# in-15a-single.net
KiCad netlist of a schematic drawn in EAGLE
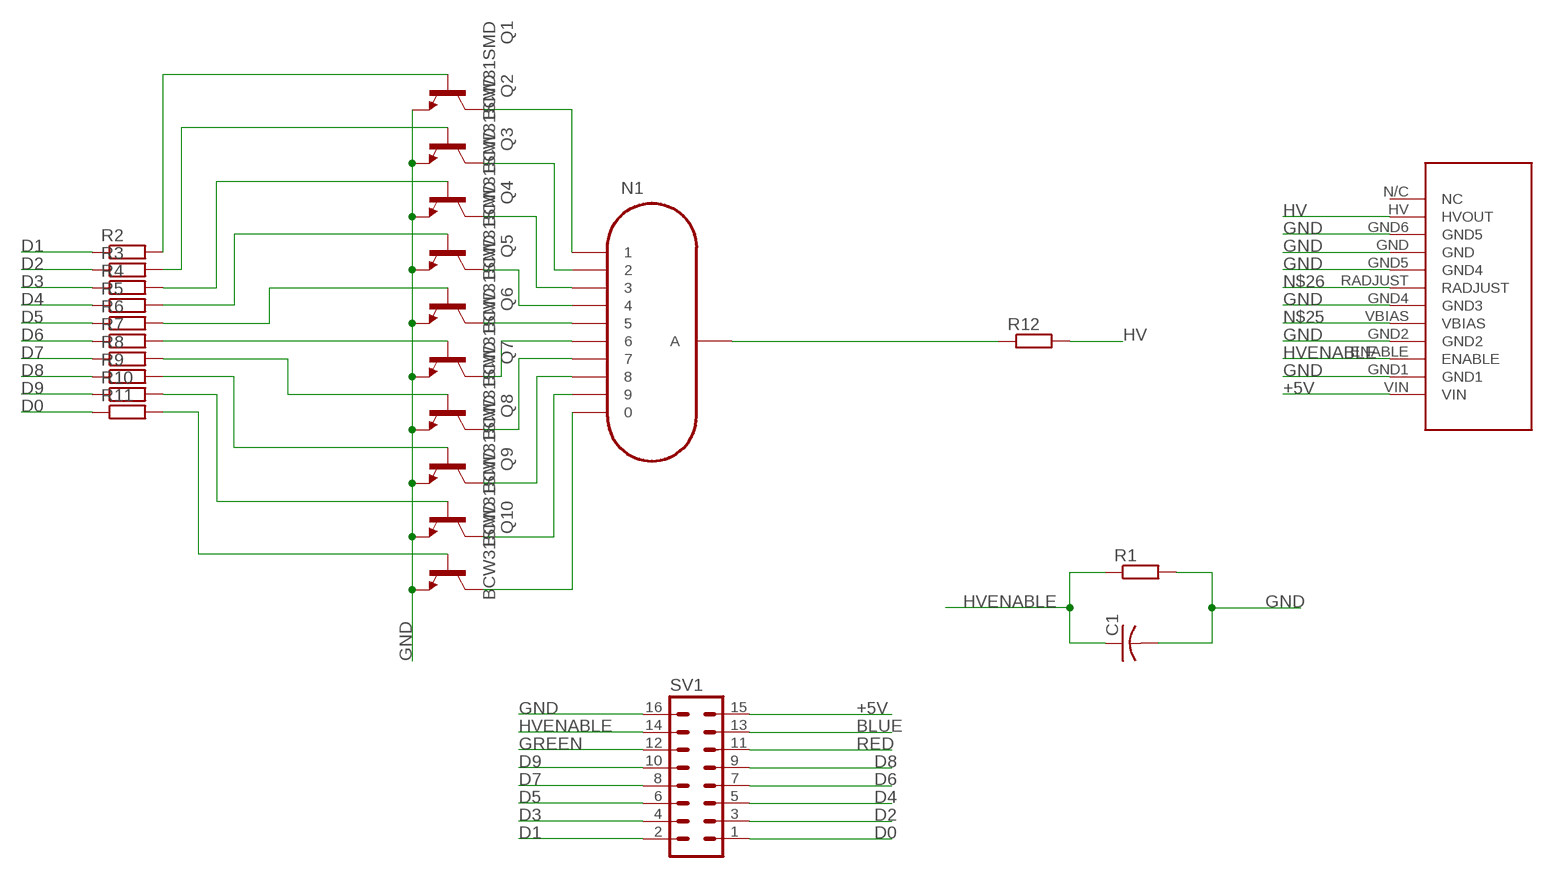
[diagram p0: schematic, sheet 1]

(export (version "E")
  (design (tool "Eeschema 10.0.6"))
  (components
    (comp (ref "C1")
      (value "C-USC0805")
      (footprint "eagle-import:C0805")
      (libsource (lib "eagle-import") (part "C-USC0805"))
    )
    (comp (ref "N1")
      (value "IN-12A")
      (footprint "eagle-import:IN-12-BIG")
      (libsource (lib "eagle-import") (part "IN-12A"))
    )
    (comp (ref "Q1")
      (value "BCW31SMD")
      (footprint "eagle-import:SOT23-BEC")
      (libsource (lib "eagle-import") (part "BCW31SMD"))
    )
    (comp (ref "Q2")
      (value "BCW31SMD")
      (footprint "eagle-import:SOT23-BEC")
      (libsource (lib "eagle-import") (part "BCW31SMD"))
    )
    (comp (ref "Q3")
      (value "BCW31SMD")
      (footprint "eagle-import:SOT23-BEC")
      (libsource (lib "eagle-import") (part "BCW31SMD"))
    )
    (comp (ref "Q4")
      (value "BCW31SMD")
      (footprint "eagle-import:SOT23-BEC")
      (libsource (lib "eagle-import") (part "BCW31SMD"))
    )
    (comp (ref "Q5")
      (value "BCW31SMD")
      (footprint "eagle-import:SOT23-BEC")
      (libsource (lib "eagle-import") (part "BCW31SMD"))
    )
    (comp (ref "Q6")
      (value "BCW31SMD")
      (footprint "eagle-import:SOT23-BEC")
      (libsource (lib "eagle-import") (part "BCW31SMD"))
    )
    (comp (ref "Q7")
      (value "BCW31SMD")
      (footprint "eagle-import:SOT23-BEC")
      (libsource (lib "eagle-import") (part "BCW31SMD"))
    )
    (comp (ref "Q8")
      (value "BCW31SMD")
      (footprint "eagle-import:SOT23-BEC")
      (libsource (lib "eagle-import") (part "BCW31SMD"))
    )
    (comp (ref "Q9")
      (value "BCW31SMD")
      (footprint "eagle-import:SOT23-BEC")
      (libsource (lib "eagle-import") (part "BCW31SMD"))
    )
    (comp (ref "Q10")
      (value "BCW31SMD")
      (footprint "eagle-import:SOT23-BEC")
      (libsource (lib "eagle-import") (part "BCW31SMD"))
    )
    (comp (ref "R1")
      (value "R-EU_M0805")
      (footprint "eagle-import:M0805")
      (libsource (lib "eagle-import") (part "R-EU_M0805"))
    )
    (comp (ref "R2")
      (value "R-EU_M0805")
      (footprint "eagle-import:M0805")
      (libsource (lib "eagle-import") (part "R-EU_M0805"))
    )
    (comp (ref "R3")
      (value "R-EU_M0805")
      (footprint "eagle-import:M0805")
      (libsource (lib "eagle-import") (part "R-EU_M0805"))
    )
    (comp (ref "R4")
      (value "R-EU_M0805")
      (footprint "eagle-import:M0805")
      (libsource (lib "eagle-import") (part "R-EU_M0805"))
    )
    (comp (ref "R5")
      (value "R-EU_M0805")
      (footprint "eagle-import:M0805")
      (libsource (lib "eagle-import") (part "R-EU_M0805"))
    )
    (comp (ref "R6")
      (value "R-EU_M0805")
      (footprint "eagle-import:M0805")
      (libsource (lib "eagle-import") (part "R-EU_M0805"))
    )
    (comp (ref "R7")
      (value "R-EU_M0805")
      (footprint "eagle-import:M0805")
      (libsource (lib "eagle-import") (part "R-EU_M0805"))
    )
    (comp (ref "R8")
      (value "R-EU_M0805")
      (footprint "eagle-import:M0805")
      (libsource (lib "eagle-import") (part "R-EU_M0805"))
    )
    (comp (ref "R9")
      (value "R-EU_M0805")
      (footprint "eagle-import:M0805")
      (libsource (lib "eagle-import") (part "R-EU_M0805"))
    )
    (comp (ref "R10")
      (value "R-EU_M0805")
      (footprint "eagle-import:M0805")
      (libsource (lib "eagle-import") (part "R-EU_M0805"))
    )
    (comp (ref "R11")
      (value "R-EU_M0805")
      (footprint "eagle-import:M0805")
      (libsource (lib "eagle-import") (part "R-EU_M0805"))
    )
    (comp (ref "R12")
      (value "R-EU_M0805")
      (footprint "eagle-import:M0805")
      (libsource (lib "eagle-import") (part "R-EU_M0805"))
    )
    (comp (ref "SV1")
      (value "ML16")
      (footprint "eagle-import:ML16")
      (libsource (lib "eagle-import") (part "ML16"))
    )
    (comp (ref "U$1")
      (value "HV-MODULE-EBAY")
      (footprint "eagle-import:NIIE-HV")
      (libsource (lib "eagle-import") (part "HV-MODULE-EBAY"))
    )
  )
  (nets
    (net (code "1") (name "/+5V") (class "Default")
      (node (ref "SV1") (pin "15") (pinfunction "15_15") (pintype "passive"))
      (node (ref "U$1") (pin "VIN") (pinfunction "VIN_VIN") (pintype "bidirectional"))
    )
    (net (code "2") (name "/BLUE") (class "Default")
      (node (ref "SV1") (pin "13") (pinfunction "13_13") (pintype "passive"))
    )
    (net (code "3") (name "/D0") (class "Default")
      (node (ref "R11") (pin "1") (pinfunction "1_1") (pintype "passive"))
      (node (ref "SV1") (pin "1") (pinfunction "1_1") (pintype "passive"))
    )
    (net (code "4") (name "/D1") (class "Default")
      (node (ref "R2") (pin "1") (pinfunction "1_1") (pintype "passive"))
      (node (ref "SV1") (pin "2") (pinfunction "2_2") (pintype "passive"))
    )
    (net (code "5") (name "/D2") (class "Default")
      (node (ref "R3") (pin "1") (pinfunction "1_1") (pintype "passive"))
      (node (ref "SV1") (pin "3") (pinfunction "3_3") (pintype "passive"))
    )
    (net (code "6") (name "/D3") (class "Default")
      (node (ref "R4") (pin "1") (pinfunction "1_1") (pintype "passive"))
      (node (ref "SV1") (pin "4") (pinfunction "4_4") (pintype "passive"))
    )
    (net (code "7") (name "/D4") (class "Default")
      (node (ref "R5") (pin "1") (pinfunction "1_1") (pintype "passive"))
      (node (ref "SV1") (pin "5") (pinfunction "5_5") (pintype "passive"))
    )
    (net (code "8") (name "/D5") (class "Default")
      (node (ref "R6") (pin "1") (pinfunction "1_1") (pintype "passive"))
      (node (ref "SV1") (pin "6") (pinfunction "6_6") (pintype "passive"))
    )
    (net (code "9") (name "/D6") (class "Default")
      (node (ref "R7") (pin "1") (pinfunction "1_1") (pintype "passive"))
      (node (ref "SV1") (pin "7") (pinfunction "7_7") (pintype "passive"))
    )
    (net (code "10") (name "/D7") (class "Default")
      (node (ref "R8") (pin "1") (pinfunction "1_1") (pintype "passive"))
      (node (ref "SV1") (pin "8") (pinfunction "8_8") (pintype "passive"))
    )
    (net (code "11") (name "/D8") (class "Default")
      (node (ref "R9") (pin "1") (pinfunction "1_1") (pintype "passive"))
      (node (ref "SV1") (pin "9") (pinfunction "9_9") (pintype "passive"))
    )
    (net (code "12") (name "/D9") (class "Default")
      (node (ref "R10") (pin "1") (pinfunction "1_1") (pintype "passive"))
      (node (ref "SV1") (pin "10") (pinfunction "10_10") (pintype "passive"))
    )
    (net (code "13") (name "/GND") (class "Default")
      (node (ref "C1") (pin "2") (pinfunction "2_2") (pintype "passive"))
      (node (ref "Q1") (pin "E") (pinfunction "E_E") (pintype "passive"))
      (node (ref "Q10") (pin "E") (pinfunction "E_E") (pintype "passive"))
      (node (ref "Q2") (pin "E") (pinfunction "E_E") (pintype "passive"))
      (node (ref "Q3") (pin "E") (pinfunction "E_E") (pintype "passive"))
      (node (ref "Q4") (pin "E") (pinfunction "E_E") (pintype "passive"))
      (node (ref "Q5") (pin "E") (pinfunction "E_E") (pintype "passive"))
      (node (ref "Q6") (pin "E") (pinfunction "E_E") (pintype "passive"))
      (node (ref "Q7") (pin "E") (pinfunction "E_E") (pintype "passive"))
      (node (ref "Q8") (pin "E") (pinfunction "E_E") (pintype "passive"))
      (node (ref "Q9") (pin "E") (pinfunction "E_E") (pintype "passive"))
      (node (ref "R1") (pin "2") (pinfunction "2_2") (pintype "passive"))
      (node (ref "SV1") (pin "16") (pinfunction "16_16") (pintype "passive"))
      (node (ref "U$1") (pin "GND") (pinfunction "GND_GND") (pintype "bidirectional"))
      (node (ref "U$1") (pin "GND1") (pinfunction "GND1_GND1") (pintype "bidirectional"))
      (node (ref "U$1") (pin "GND2") (pinfunction "GND2_GND2") (pintype "bidirectional"))
      (node (ref "U$1") (pin "GND4") (pinfunction "GND3_GND4") (pintype "bidirectional"))
      (node (ref "U$1") (pin "GND5") (pinfunction "GND4_GND5") (pintype "bidirectional"))
      (node (ref "U$1") (pin "GND6") (pinfunction "GND5_GND6") (pintype "bidirectional"))
    )
    (net (code "14") (name "/GREEN") (class "Default")
      (node (ref "SV1") (pin "12") (pinfunction "12_12") (pintype "passive"))
    )
    (net (code "15") (name "/HV") (class "Default")
      (node (ref "R12") (pin "2") (pinfunction "2_2") (pintype "passive"))
      (node (ref "U$1") (pin "HV") (pinfunction "HVOUT_HV") (pintype "bidirectional"))
    )
    (net (code "16") (name "/HVENABLE") (class "Default")
      (node (ref "C1") (pin "1") (pinfunction "1_1") (pintype "passive"))
      (node (ref "R1") (pin "1") (pinfunction "1_1") (pintype "passive"))
      (node (ref "SV1") (pin "14") (pinfunction "14_14") (pintype "passive"))
      (node (ref "U$1") (pin "ENABLE") (pinfunction "ENABLE_ENABLE") (pintype "bidirectional"))
    )
    (net (code "17") (name "/N$25") (class "Default")
      (node (ref "U$1") (pin "VBIAS") (pinfunction "VBIAS_VBIAS") (pintype "bidirectional"))
    )
    (net (code "18") (name "/N$26") (class "Default")
      (node (ref "U$1") (pin "RADJUST") (pinfunction "RADJUST_RADJUST") (pintype "bidirectional"))
    )
    (net (code "19") (name "/RED") (class "Default")
      (node (ref "SV1") (pin "11") (pinfunction "11_11") (pintype "passive"))
    )
    (net (code "20") (name "Net-(N1-Pad0)") (class "Default")
      (node (ref "N1") (pin "0") (pinfunction "0_0") (pintype "bidirectional"))
      (node (ref "Q10") (pin "C") (pinfunction "C_C") (pintype "passive"))
    )
    (net (code "21") (name "Net-(N1-Pad1)") (class "Default")
      (node (ref "N1") (pin "1") (pinfunction "1_1") (pintype "bidirectional"))
      (node (ref "Q1") (pin "C") (pinfunction "C_C") (pintype "passive"))
    )
    (net (code "22") (name "Net-(N1-Pad2)") (class "Default")
      (node (ref "N1") (pin "2") (pinfunction "2_2") (pintype "bidirectional"))
      (node (ref "Q2") (pin "C") (pinfunction "C_C") (pintype "passive"))
    )
    (net (code "23") (name "Net-(N1-Pad3)") (class "Default")
      (node (ref "N1") (pin "3") (pinfunction "3_3") (pintype "bidirectional"))
      (node (ref "Q3") (pin "C") (pinfunction "C_C") (pintype "passive"))
    )
    (net (code "24") (name "Net-(N1-Pad4)") (class "Default")
      (node (ref "N1") (pin "4") (pinfunction "4_4") (pintype "bidirectional"))
      (node (ref "Q4") (pin "C") (pinfunction "C_C") (pintype "passive"))
    )
    (net (code "25") (name "Net-(N1-Pad5)") (class "Default")
      (node (ref "N1") (pin "5") (pinfunction "5_5") (pintype "bidirectional"))
      (node (ref "Q5") (pin "C") (pinfunction "C_C") (pintype "passive"))
    )
    (net (code "26") (name "Net-(N1-Pad6)") (class "Default")
      (node (ref "N1") (pin "6") (pinfunction "6_6") (pintype "bidirectional"))
      (node (ref "Q6") (pin "C") (pinfunction "C_C") (pintype "passive"))
    )
    (net (code "27") (name "Net-(N1-Pad7)") (class "Default")
      (node (ref "N1") (pin "7") (pinfunction "7_7") (pintype "bidirectional"))
      (node (ref "Q7") (pin "C") (pinfunction "C_C") (pintype "passive"))
    )
    (net (code "28") (name "Net-(N1-Pad8)") (class "Default")
      (node (ref "N1") (pin "8") (pinfunction "8_8") (pintype "bidirectional"))
      (node (ref "Q8") (pin "C") (pinfunction "C_C") (pintype "passive"))
    )
    (net (code "29") (name "Net-(N1-Pad9)") (class "Default")
      (node (ref "N1") (pin "9") (pinfunction "9_9") (pintype "bidirectional"))
      (node (ref "Q9") (pin "C") (pinfunction "C_C") (pintype "passive"))
    )
    (net (code "30") (name "Net-(N1-PadA)") (class "Default")
      (node (ref "N1") (pin "A") (pinfunction "A_A") (pintype "bidirectional"))
      (node (ref "R12") (pin "1") (pinfunction "1_1") (pintype "passive"))
    )
    (net (code "31") (name "Net-(Q1-PadB)") (class "Default")
      (node (ref "Q1") (pin "B") (pinfunction "B_B") (pintype "passive"))
      (node (ref "R2") (pin "2") (pinfunction "2_2") (pintype "passive"))
    )
    (net (code "32") (name "Net-(Q2-PadB)") (class "Default")
      (node (ref "Q2") (pin "B") (pinfunction "B_B") (pintype "passive"))
      (node (ref "R3") (pin "2") (pinfunction "2_2") (pintype "passive"))
    )
    (net (code "33") (name "Net-(Q3-PadB)") (class "Default")
      (node (ref "Q3") (pin "B") (pinfunction "B_B") (pintype "passive"))
      (node (ref "R4") (pin "2") (pinfunction "2_2") (pintype "passive"))
    )
    (net (code "34") (name "Net-(Q4-PadB)") (class "Default")
      (node (ref "Q4") (pin "B") (pinfunction "B_B") (pintype "passive"))
      (node (ref "R5") (pin "2") (pinfunction "2_2") (pintype "passive"))
    )
    (net (code "35") (name "Net-(Q5-PadB)") (class "Default")
      (node (ref "Q5") (pin "B") (pinfunction "B_B") (pintype "passive"))
      (node (ref "R6") (pin "2") (pinfunction "2_2") (pintype "passive"))
    )
    (net (code "36") (name "Net-(Q6-PadB)") (class "Default")
      (node (ref "Q6") (pin "B") (pinfunction "B_B") (pintype "passive"))
      (node (ref "R7") (pin "2") (pinfunction "2_2") (pintype "passive"))
    )
    (net (code "37") (name "Net-(Q7-PadB)") (class "Default")
      (node (ref "Q7") (pin "B") (pinfunction "B_B") (pintype "passive"))
      (node (ref "R8") (pin "2") (pinfunction "2_2") (pintype "passive"))
    )
    (net (code "38") (name "Net-(Q8-PadB)") (class "Default")
      (node (ref "Q8") (pin "B") (pinfunction "B_B") (pintype "passive"))
      (node (ref "R9") (pin "2") (pinfunction "2_2") (pintype "passive"))
    )
    (net (code "39") (name "Net-(Q9-PadB)") (class "Default")
      (node (ref "Q9") (pin "B") (pinfunction "B_B") (pintype "passive"))
      (node (ref "R10") (pin "2") (pinfunction "2_2") (pintype "passive"))
    )
    (net (code "40") (name "Net-(Q10-PadB)") (class "Default")
      (node (ref "Q10") (pin "B") (pinfunction "B_B") (pintype "passive"))
      (node (ref "R11") (pin "2") (pinfunction "2_2") (pintype "passive"))
    )
    (net (code "41") (name "unconnected-(U$1-NC-PadN{slash}C)") (class "Default")
      (node (ref "U$1") (pin "N/C") (pinfunction "NC_N/C") (pintype "bidirectional"))
    )
  )
)
